# LED2.net
KiCad netlist of a schematic drawn in EAGLE
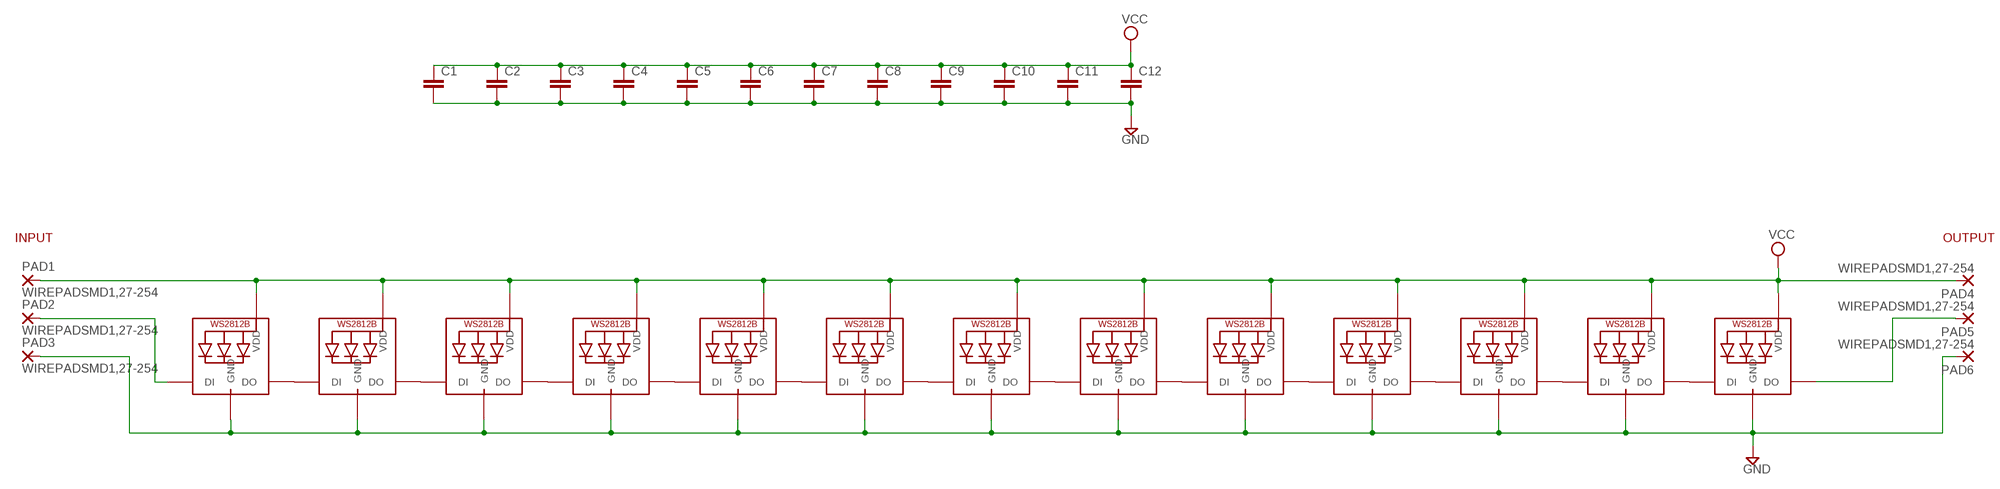
[diagram p0: schematic, sheet 1]

(export (version "E")
  (design (tool "Eeschema 10.0.6"))
  (components
    (comp (ref "C1")
      (value "C-EUC0805K")
      (footprint "eagle-import:C0805K")
      (libsource (lib "eagle-import") (part "C-EUC0805K"))
    )
    (comp (ref "C2")
      (value "C-EUC0805K")
      (footprint "eagle-import:C0805K")
      (libsource (lib "eagle-import") (part "C-EUC0805K"))
    )
    (comp (ref "C3")
      (value "C-EUC0805K")
      (footprint "eagle-import:C0805K")
      (libsource (lib "eagle-import") (part "C-EUC0805K"))
    )
    (comp (ref "C4")
      (value "C-EUC0805K")
      (footprint "eagle-import:C0805K")
      (libsource (lib "eagle-import") (part "C-EUC0805K"))
    )
    (comp (ref "C5")
      (value "C-EUC0805K")
      (footprint "eagle-import:C0805K")
      (libsource (lib "eagle-import") (part "C-EUC0805K"))
    )
    (comp (ref "C6")
      (value "C-EUC0805K")
      (footprint "eagle-import:C0805K")
      (libsource (lib "eagle-import") (part "C-EUC0805K"))
    )
    (comp (ref "C7")
      (value "C-EUC0805K")
      (footprint "eagle-import:C0805K")
      (libsource (lib "eagle-import") (part "C-EUC0805K"))
    )
    (comp (ref "C8")
      (value "C-EUC0805K")
      (footprint "eagle-import:C0805K")
      (libsource (lib "eagle-import") (part "C-EUC0805K"))
    )
    (comp (ref "C9")
      (value "C-EUC0805K")
      (footprint "eagle-import:C0805K")
      (libsource (lib "eagle-import") (part "C-EUC0805K"))
    )
    (comp (ref "C10")
      (value "C-EUC0805K")
      (footprint "eagle-import:C0805K")
      (libsource (lib "eagle-import") (part "C-EUC0805K"))
    )
    (comp (ref "C11")
      (value "C-EUC0805K")
      (footprint "eagle-import:C0805K")
      (libsource (lib "eagle-import") (part "C-EUC0805K"))
    )
    (comp (ref "C12")
      (value "C-EUC0805K")
      (footprint "eagle-import:C0805K")
      (libsource (lib "eagle-import") (part "C-EUC0805K"))
    )
    (comp (ref "LED1")
      (value "WS2812B5050")
      (footprint "eagle-import:WS2812B")
      (libsource (lib "eagle-import") (part "WS2812B5050"))
    )
    (comp (ref "LED2")
      (value "WS2812B5050")
      (footprint "eagle-import:WS2812B")
      (libsource (lib "eagle-import") (part "WS2812B5050"))
    )
    (comp (ref "LED3")
      (value "WS2812B5050")
      (footprint "eagle-import:WS2812B")
      (libsource (lib "eagle-import") (part "WS2812B5050"))
    )
    (comp (ref "LED4")
      (value "WS2812B5050")
      (footprint "eagle-import:WS2812B")
      (libsource (lib "eagle-import") (part "WS2812B5050"))
    )
    (comp (ref "LED5")
      (value "WS2812B5050")
      (footprint "eagle-import:WS2812B")
      (libsource (lib "eagle-import") (part "WS2812B5050"))
    )
    (comp (ref "LED6")
      (value "WS2812B5050")
      (footprint "eagle-import:WS2812B")
      (libsource (lib "eagle-import") (part "WS2812B5050"))
    )
    (comp (ref "LED7")
      (value "WS2812B5050")
      (footprint "eagle-import:WS2812B")
      (libsource (lib "eagle-import") (part "WS2812B5050"))
    )
    (comp (ref "LED8")
      (value "WS2812B5050")
      (footprint "eagle-import:WS2812B")
      (libsource (lib "eagle-import") (part "WS2812B5050"))
    )
    (comp (ref "LED9")
      (value "WS2812B5050")
      (footprint "eagle-import:WS2812B")
      (libsource (lib "eagle-import") (part "WS2812B5050"))
    )
    (comp (ref "LED10")
      (value "WS2812B5050")
      (footprint "eagle-import:WS2812B")
      (libsource (lib "eagle-import") (part "WS2812B5050"))
    )
    (comp (ref "LED11")
      (value "WS2812B5050")
      (footprint "eagle-import:WS2812B")
      (libsource (lib "eagle-import") (part "WS2812B5050"))
    )
    (comp (ref "LED12")
      (value "WS2812B5050")
      (footprint "eagle-import:WS2812B")
      (libsource (lib "eagle-import") (part "WS2812B5050"))
    )
    (comp (ref "LED13")
      (value "WS2812B5050")
      (footprint "eagle-import:WS2812B")
      (libsource (lib "eagle-import") (part "WS2812B5050"))
    )
    (comp (ref "PAD1")
      (value "WIREPADSMD1,27-254")
      (footprint "eagle-import:SMD1,27-2,54")
      (libsource (lib "eagle-import") (part "WIREPADSMD1,27-254"))
    )
    (comp (ref "PAD2")
      (value "WIREPADSMD1,27-254")
      (footprint "eagle-import:SMD1,27-2,54")
      (libsource (lib "eagle-import") (part "WIREPADSMD1,27-254"))
    )
    (comp (ref "PAD3")
      (value "WIREPADSMD1,27-254")
      (footprint "eagle-import:SMD1,27-2,54")
      (libsource (lib "eagle-import") (part "WIREPADSMD1,27-254"))
    )
    (comp (ref "PAD4")
      (value "WIREPADSMD1,27-254")
      (footprint "eagle-import:SMD1,27-2,54")
      (libsource (lib "eagle-import") (part "WIREPADSMD1,27-254"))
    )
    (comp (ref "PAD5")
      (value "WIREPADSMD1,27-254")
      (footprint "eagle-import:SMD1,27-2,54")
      (libsource (lib "eagle-import") (part "WIREPADSMD1,27-254"))
    )
    (comp (ref "PAD6")
      (value "WIREPADSMD1,27-254")
      (footprint "eagle-import:SMD1,27-2,54")
      (libsource (lib "eagle-import") (part "WIREPADSMD1,27-254"))
    )
  )
  (nets
    (net (code "1") (name "GND") (class "Default")
      (node (ref "C1") (pin "2") (pinfunction "2_2") (pintype "passive"))
      (node (ref "C10") (pin "2") (pinfunction "2_2") (pintype "passive"))
      (node (ref "C11") (pin "2") (pinfunction "2_2") (pintype "passive"))
      (node (ref "C12") (pin "2") (pinfunction "2_2") (pintype "passive"))
      (node (ref "C2") (pin "2") (pinfunction "2_2") (pintype "passive"))
      (node (ref "C3") (pin "2") (pinfunction "2_2") (pintype "passive"))
      (node (ref "C4") (pin "2") (pinfunction "2_2") (pintype "passive"))
      (node (ref "C5") (pin "2") (pinfunction "2_2") (pintype "passive"))
      (node (ref "C6") (pin "2") (pinfunction "2_2") (pintype "passive"))
      (node (ref "C7") (pin "2") (pinfunction "2_2") (pintype "passive"))
      (node (ref "C8") (pin "2") (pinfunction "2_2") (pintype "passive"))
      (node (ref "C9") (pin "2") (pinfunction "2_2") (pintype "passive"))
      (node (ref "LED1") (pin "3-GND") (pinfunction "GND_3-GND") (pintype "power_in"))
      (node (ref "LED10") (pin "3-GND") (pinfunction "GND_3-GND") (pintype "power_in"))
      (node (ref "LED11") (pin "3-GND") (pinfunction "GND_3-GND") (pintype "power_in"))
      (node (ref "LED12") (pin "3-GND") (pinfunction "GND_3-GND") (pintype "power_in"))
      (node (ref "LED13") (pin "3-GND") (pinfunction "GND_3-GND") (pintype "power_in"))
      (node (ref "LED2") (pin "3-GND") (pinfunction "GND_3-GND") (pintype "power_in"))
      (node (ref "LED3") (pin "3-GND") (pinfunction "GND_3-GND") (pintype "power_in"))
      (node (ref "LED4") (pin "3-GND") (pinfunction "GND_3-GND") (pintype "power_in"))
      (node (ref "LED5") (pin "3-GND") (pinfunction "GND_3-GND") (pintype "power_in"))
      (node (ref "LED6") (pin "3-GND") (pinfunction "GND_3-GND") (pintype "power_in"))
      (node (ref "LED7") (pin "3-GND") (pinfunction "GND_3-GND") (pintype "power_in"))
      (node (ref "LED8") (pin "3-GND") (pinfunction "GND_3-GND") (pintype "power_in"))
      (node (ref "LED9") (pin "3-GND") (pinfunction "GND_3-GND") (pintype "power_in"))
      (node (ref "PAD3") (pin "1") (pinfunction "P_1") (pintype "passive"))
      (node (ref "PAD6") (pin "1") (pinfunction "P_1") (pintype "passive"))
    )
    (net (code "2") (name "Net-(LED1-DI)") (class "Default")
      (node (ref "LED1") (pin "4-DIN") (pinfunction "DI_4-DIN") (pintype "input"))
      (node (ref "PAD2") (pin "1") (pinfunction "P_1") (pintype "passive"))
    )
    (net (code "3") (name "Net-(LED1-DO)") (class "Default")
      (node (ref "LED1") (pin "2-DOUT") (pinfunction "DO_2-DOUT") (pintype "output"))
      (node (ref "LED2") (pin "4-DIN") (pinfunction "DI_4-DIN") (pintype "input"))
    )
    (net (code "4") (name "Net-(LED2-DO)") (class "Default")
      (node (ref "LED2") (pin "2-DOUT") (pinfunction "DO_2-DOUT") (pintype "output"))
      (node (ref "LED3") (pin "4-DIN") (pinfunction "DI_4-DIN") (pintype "input"))
    )
    (net (code "5") (name "Net-(LED3-DO)") (class "Default")
      (node (ref "LED3") (pin "2-DOUT") (pinfunction "DO_2-DOUT") (pintype "output"))
      (node (ref "LED4") (pin "4-DIN") (pinfunction "DI_4-DIN") (pintype "input"))
    )
    (net (code "6") (name "Net-(LED4-DO)") (class "Default")
      (node (ref "LED4") (pin "2-DOUT") (pinfunction "DO_2-DOUT") (pintype "output"))
      (node (ref "LED5") (pin "4-DIN") (pinfunction "DI_4-DIN") (pintype "input"))
    )
    (net (code "7") (name "Net-(LED5-DO)") (class "Default")
      (node (ref "LED5") (pin "2-DOUT") (pinfunction "DO_2-DOUT") (pintype "output"))
      (node (ref "LED6") (pin "4-DIN") (pinfunction "DI_4-DIN") (pintype "input"))
    )
    (net (code "8") (name "Net-(LED6-DO)") (class "Default")
      (node (ref "LED6") (pin "2-DOUT") (pinfunction "DO_2-DOUT") (pintype "output"))
      (node (ref "LED7") (pin "4-DIN") (pinfunction "DI_4-DIN") (pintype "input"))
    )
    (net (code "9") (name "Net-(LED7-DO)") (class "Default")
      (node (ref "LED7") (pin "2-DOUT") (pinfunction "DO_2-DOUT") (pintype "output"))
      (node (ref "LED8") (pin "4-DIN") (pinfunction "DI_4-DIN") (pintype "input"))
    )
    (net (code "10") (name "Net-(LED8-DO)") (class "Default")
      (node (ref "LED8") (pin "2-DOUT") (pinfunction "DO_2-DOUT") (pintype "output"))
      (node (ref "LED9") (pin "4-DIN") (pinfunction "DI_4-DIN") (pintype "input"))
    )
    (net (code "11") (name "Net-(LED10-DI)") (class "Default")
      (node (ref "LED10") (pin "4-DIN") (pinfunction "DI_4-DIN") (pintype "input"))
      (node (ref "LED9") (pin "2-DOUT") (pinfunction "DO_2-DOUT") (pintype "output"))
    )
    (net (code "12") (name "Net-(LED10-DO)") (class "Default")
      (node (ref "LED10") (pin "2-DOUT") (pinfunction "DO_2-DOUT") (pintype "output"))
      (node (ref "LED11") (pin "4-DIN") (pinfunction "DI_4-DIN") (pintype "input"))
    )
    (net (code "13") (name "Net-(LED11-DO)") (class "Default")
      (node (ref "LED11") (pin "2-DOUT") (pinfunction "DO_2-DOUT") (pintype "output"))
      (node (ref "LED12") (pin "4-DIN") (pinfunction "DI_4-DIN") (pintype "input"))
    )
    (net (code "14") (name "Net-(LED12-DO)") (class "Default")
      (node (ref "LED12") (pin "2-DOUT") (pinfunction "DO_2-DOUT") (pintype "output"))
      (node (ref "LED13") (pin "4-DIN") (pinfunction "DI_4-DIN") (pintype "input"))
    )
    (net (code "15") (name "Net-(LED13-DO)") (class "Default")
      (node (ref "LED13") (pin "2-DOUT") (pinfunction "DO_2-DOUT") (pintype "output"))
      (node (ref "PAD5") (pin "1") (pinfunction "P_1") (pintype "passive"))
    )
    (net (code "16") (name "VCC") (class "Default")
      (node (ref "C1") (pin "1") (pinfunction "1_1") (pintype "passive"))
      (node (ref "C10") (pin "1") (pinfunction "1_1") (pintype "passive"))
      (node (ref "C11") (pin "1") (pinfunction "1_1") (pintype "passive"))
      (node (ref "C12") (pin "1") (pinfunction "1_1") (pintype "passive"))
      (node (ref "C2") (pin "1") (pinfunction "1_1") (pintype "passive"))
      (node (ref "C3") (pin "1") (pinfunction "1_1") (pintype "passive"))
      (node (ref "C4") (pin "1") (pinfunction "1_1") (pintype "passive"))
      (node (ref "C5") (pin "1") (pinfunction "1_1") (pintype "passive"))
      (node (ref "C6") (pin "1") (pinfunction "1_1") (pintype "passive"))
      (node (ref "C7") (pin "1") (pinfunction "1_1") (pintype "passive"))
      (node (ref "C8") (pin "1") (pinfunction "1_1") (pintype "passive"))
      (node (ref "C9") (pin "1") (pinfunction "1_1") (pintype "passive"))
      (node (ref "LED1") (pin "1-VDD") (pinfunction "VDD_1-VDD") (pintype "power_in"))
      (node (ref "LED10") (pin "1-VDD") (pinfunction "VDD_1-VDD") (pintype "power_in"))
      (node (ref "LED11") (pin "1-VDD") (pinfunction "VDD_1-VDD") (pintype "power_in"))
      (node (ref "LED12") (pin "1-VDD") (pinfunction "VDD_1-VDD") (pintype "power_in"))
      (node (ref "LED13") (pin "1-VDD") (pinfunction "VDD_1-VDD") (pintype "power_in"))
      (node (ref "LED2") (pin "1-VDD") (pinfunction "VDD_1-VDD") (pintype "power_in"))
      (node (ref "LED3") (pin "1-VDD") (pinfunction "VDD_1-VDD") (pintype "power_in"))
      (node (ref "LED4") (pin "1-VDD") (pinfunction "VDD_1-VDD") (pintype "power_in"))
      (node (ref "LED5") (pin "1-VDD") (pinfunction "VDD_1-VDD") (pintype "power_in"))
      (node (ref "LED6") (pin "1-VDD") (pinfunction "VDD_1-VDD") (pintype "power_in"))
      (node (ref "LED7") (pin "1-VDD") (pinfunction "VDD_1-VDD") (pintype "power_in"))
      (node (ref "LED8") (pin "1-VDD") (pinfunction "VDD_1-VDD") (pintype "power_in"))
      (node (ref "LED9") (pin "1-VDD") (pinfunction "VDD_1-VDD") (pintype "power_in"))
      (node (ref "PAD1") (pin "1") (pinfunction "P_1") (pintype "passive"))
      (node (ref "PAD4") (pin "1") (pinfunction "P_1") (pintype "passive"))
    )
  )
)
